# Connector_to_Connector.net
KiCad netlist of a schematic drawn in Altium Designer
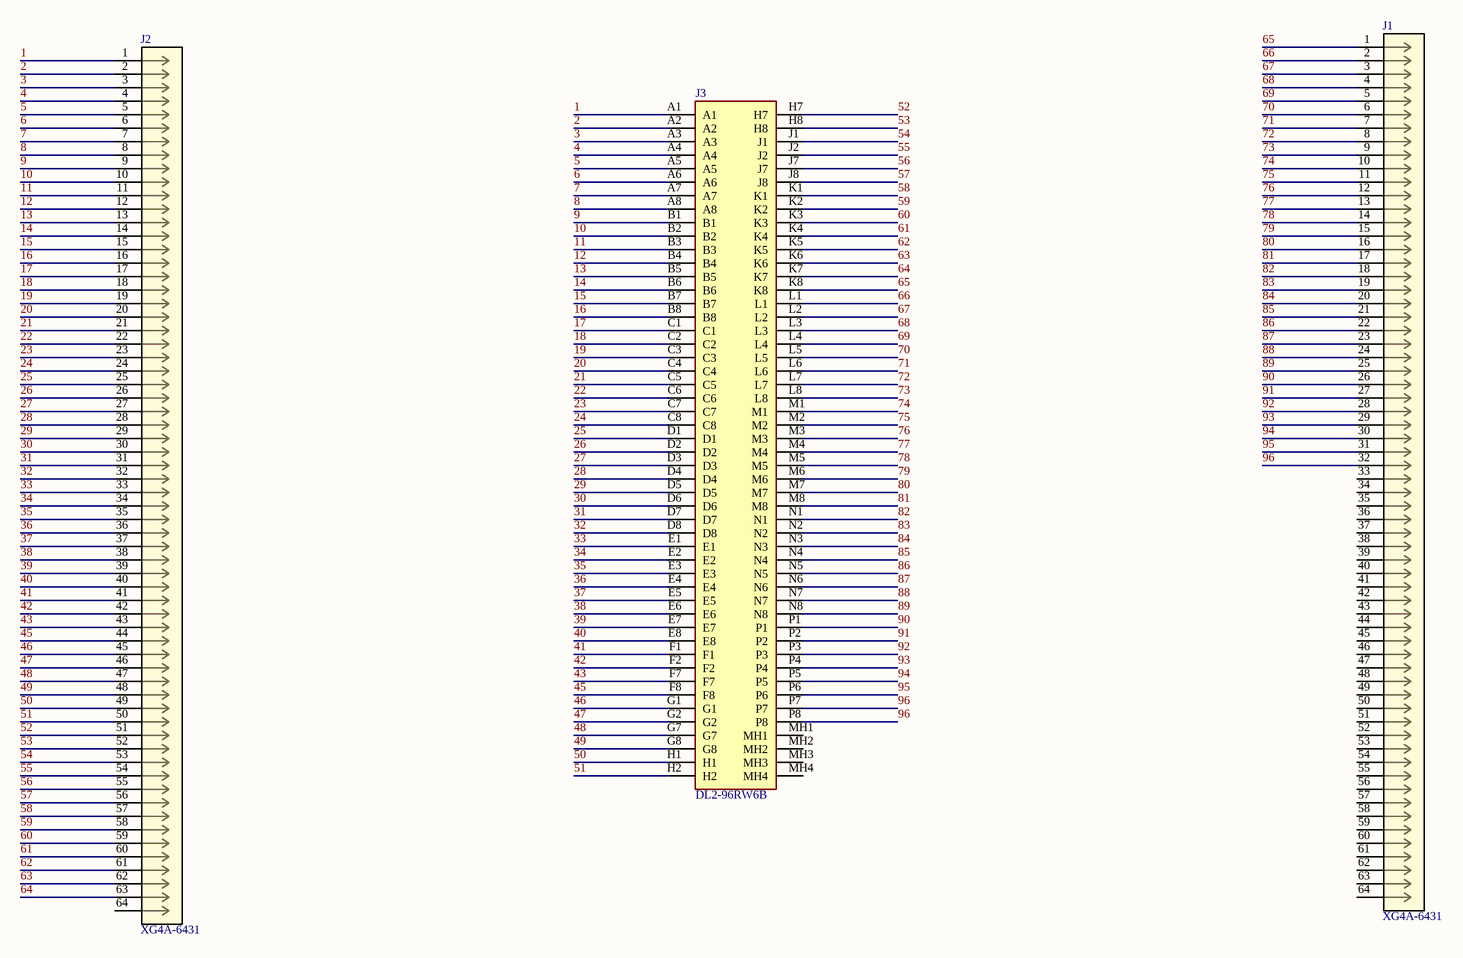
[diagram p0: Connector to Connector.SchDoc]

(export (version "E")
  (design (tool "Eeschema 10.0.6"))
  (components
    (comp (ref "J1")
      (value "XG4A-6431")
      (footprint "CONN_XG4A-6431_OMR")
      (description "No Description Available")
      (fields (field (name "COPYRIGHT") "Copyright (C) 2023 Ultra Librarian. All rights reserved."))
      (libsource (lib "XG4A-6431") (part "XG4A-6431"))
    )
    (comp (ref "J2")
      (value "XG4A-6431")
      (footprint "CONN_XG4A-6431_OMR")
      (description "No Description Available")
      (fields (field (name "COPYRIGHT") "Copyright (C) 2023 Ultra Librarian. All rights reserved."))
      (libsource (lib "XG4A-6431") (part "XG4A-6431"))
    )
    (comp (ref "J3")
      (value "DL2-96RW6B")
      (footprint "DL296RW6B")
      (description "Conn Rectangular SKT 96 POS 2.54mm Solder ST Thru-Hole Automotive")
      (libsource (lib "DL2-96RW6B") (part "DL2-96RW6B"))
    )
  )
  (nets
    (net (code "1") (name "/1") (class "Default")
      (node (ref "J2") (pin "1") (pinfunction "1_1") (pintype "passive"))
      (node (ref "J3") (pin "A1") (pinfunction "A1_A1") (pintype "passive"))
    )
    (net (code "2") (name "/2") (class "Default")
      (node (ref "J2") (pin "2") (pinfunction "2_2") (pintype "passive"))
      (node (ref "J3") (pin "A2") (pinfunction "A2_A2") (pintype "passive"))
    )
    (net (code "3") (name "/3") (class "Default")
      (node (ref "J2") (pin "3") (pinfunction "3_3") (pintype "passive"))
      (node (ref "J3") (pin "A3") (pinfunction "A3_A3") (pintype "passive"))
    )
    (net (code "4") (name "/4") (class "Default")
      (node (ref "J2") (pin "4") (pinfunction "4_4") (pintype "passive"))
      (node (ref "J3") (pin "A4") (pinfunction "A4_A4") (pintype "passive"))
    )
    (net (code "5") (name "/5") (class "Default")
      (node (ref "J2") (pin "5") (pinfunction "5_5") (pintype "passive"))
      (node (ref "J3") (pin "A5") (pinfunction "A5_A5") (pintype "passive"))
    )
    (net (code "6") (name "/6") (class "Default")
      (node (ref "J2") (pin "6") (pinfunction "6_6") (pintype "passive"))
      (node (ref "J3") (pin "A6") (pinfunction "A6_A6") (pintype "passive"))
    )
    (net (code "7") (name "/7") (class "Default")
      (node (ref "J2") (pin "7") (pinfunction "7_7") (pintype "passive"))
      (node (ref "J3") (pin "A7") (pinfunction "A7_A7") (pintype "passive"))
    )
    (net (code "8") (name "/8") (class "Default")
      (node (ref "J2") (pin "8") (pinfunction "8_8") (pintype "passive"))
      (node (ref "J3") (pin "A8") (pinfunction "A8_A8") (pintype "passive"))
    )
    (net (code "9") (name "/9") (class "Default")
      (node (ref "J2") (pin "9") (pinfunction "9_9") (pintype "passive"))
      (node (ref "J3") (pin "B1") (pinfunction "B1_B1") (pintype "passive"))
    )
    (net (code "10") (name "/10") (class "Default")
      (node (ref "J2") (pin "10") (pinfunction "10_10") (pintype "passive"))
      (node (ref "J3") (pin "B2") (pinfunction "B2_B2") (pintype "passive"))
    )
    (net (code "11") (name "/11") (class "Default")
      (node (ref "J2") (pin "11") (pinfunction "11_11") (pintype "passive"))
      (node (ref "J3") (pin "B3") (pinfunction "B3_B3") (pintype "passive"))
    )
    (net (code "12") (name "/12") (class "Default")
      (node (ref "J2") (pin "12") (pinfunction "12_12") (pintype "passive"))
      (node (ref "J3") (pin "B4") (pinfunction "B4_B4") (pintype "passive"))
    )
    (net (code "13") (name "/13") (class "Default")
      (node (ref "J2") (pin "13") (pinfunction "13_13") (pintype "passive"))
      (node (ref "J3") (pin "B5") (pinfunction "B5_B5") (pintype "passive"))
    )
    (net (code "14") (name "/14") (class "Default")
      (node (ref "J2") (pin "14") (pinfunction "14_14") (pintype "passive"))
      (node (ref "J3") (pin "B6") (pinfunction "B6_B6") (pintype "passive"))
    )
    (net (code "15") (name "/15") (class "Default")
      (node (ref "J2") (pin "15") (pinfunction "15_15") (pintype "passive"))
      (node (ref "J3") (pin "B7") (pinfunction "B7_B7") (pintype "passive"))
    )
    (net (code "16") (name "/16") (class "Default")
      (node (ref "J2") (pin "16") (pinfunction "16_16") (pintype "passive"))
      (node (ref "J3") (pin "B8") (pinfunction "B8_B8") (pintype "passive"))
    )
    (net (code "17") (name "/17") (class "Default")
      (node (ref "J2") (pin "17") (pinfunction "17_17") (pintype "passive"))
      (node (ref "J3") (pin "C1") (pinfunction "C1_C1") (pintype "passive"))
    )
    (net (code "18") (name "/18") (class "Default")
      (node (ref "J2") (pin "18") (pinfunction "18_18") (pintype "passive"))
      (node (ref "J3") (pin "C2") (pinfunction "C2_C2") (pintype "passive"))
    )
    (net (code "19") (name "/19") (class "Default")
      (node (ref "J2") (pin "19") (pinfunction "19_19") (pintype "passive"))
      (node (ref "J3") (pin "C3") (pinfunction "C3_C3") (pintype "passive"))
    )
    (net (code "20") (name "/20") (class "Default")
      (node (ref "J2") (pin "20") (pinfunction "20_20") (pintype "passive"))
      (node (ref "J3") (pin "C4") (pinfunction "C4_C4") (pintype "passive"))
    )
    (net (code "21") (name "/21") (class "Default")
      (node (ref "J2") (pin "21") (pinfunction "21_21") (pintype "passive"))
      (node (ref "J3") (pin "C5") (pinfunction "C5_C5") (pintype "passive"))
    )
    (net (code "22") (name "/22") (class "Default")
      (node (ref "J2") (pin "22") (pinfunction "22_22") (pintype "passive"))
      (node (ref "J3") (pin "C6") (pinfunction "C6_C6") (pintype "passive"))
    )
    (net (code "23") (name "/23") (class "Default")
      (node (ref "J2") (pin "23") (pinfunction "23_23") (pintype "passive"))
      (node (ref "J3") (pin "C7") (pinfunction "C7_C7") (pintype "passive"))
    )
    (net (code "24") (name "/24") (class "Default")
      (node (ref "J2") (pin "24") (pinfunction "24_24") (pintype "passive"))
      (node (ref "J3") (pin "C8") (pinfunction "C8_C8") (pintype "passive"))
    )
    (net (code "25") (name "/25") (class "Default")
      (node (ref "J2") (pin "25") (pinfunction "25_25") (pintype "passive"))
      (node (ref "J3") (pin "D1") (pinfunction "D1_D1") (pintype "passive"))
    )
    (net (code "26") (name "/26") (class "Default")
      (node (ref "J2") (pin "26") (pinfunction "26_26") (pintype "passive"))
      (node (ref "J3") (pin "D2") (pinfunction "D2_D2") (pintype "passive"))
    )
    (net (code "27") (name "/27") (class "Default")
      (node (ref "J2") (pin "27") (pinfunction "27_27") (pintype "passive"))
      (node (ref "J3") (pin "D3") (pinfunction "D3_D3") (pintype "passive"))
    )
    (net (code "28") (name "/28") (class "Default")
      (node (ref "J2") (pin "28") (pinfunction "28_28") (pintype "passive"))
      (node (ref "J3") (pin "D4") (pinfunction "D4_D4") (pintype "passive"))
    )
    (net (code "29") (name "/29") (class "Default")
      (node (ref "J2") (pin "29") (pinfunction "29_29") (pintype "passive"))
      (node (ref "J3") (pin "D5") (pinfunction "D5_D5") (pintype "passive"))
    )
    (net (code "30") (name "/30") (class "Default")
      (node (ref "J2") (pin "30") (pinfunction "30_30") (pintype "passive"))
      (node (ref "J3") (pin "D6") (pinfunction "D6_D6") (pintype "passive"))
    )
    (net (code "31") (name "/31") (class "Default")
      (node (ref "J2") (pin "31") (pinfunction "31_31") (pintype "passive"))
      (node (ref "J3") (pin "D7") (pinfunction "D7_D7") (pintype "passive"))
    )
    (net (code "32") (name "/32") (class "Default")
      (node (ref "J2") (pin "32") (pinfunction "32_32") (pintype "passive"))
      (node (ref "J3") (pin "D8") (pinfunction "D8_D8") (pintype "passive"))
    )
    (net (code "33") (name "/33") (class "Default")
      (node (ref "J2") (pin "33") (pinfunction "33_33") (pintype "passive"))
      (node (ref "J3") (pin "E1") (pinfunction "E1_E1") (pintype "passive"))
    )
    (net (code "34") (name "/34") (class "Default")
      (node (ref "J2") (pin "34") (pinfunction "34_34") (pintype "passive"))
      (node (ref "J3") (pin "E2") (pinfunction "E2_E2") (pintype "passive"))
    )
    (net (code "35") (name "/35") (class "Default")
      (node (ref "J2") (pin "35") (pinfunction "35_35") (pintype "passive"))
      (node (ref "J3") (pin "E3") (pinfunction "E3_E3") (pintype "passive"))
    )
    (net (code "36") (name "/36") (class "Default")
      (node (ref "J2") (pin "36") (pinfunction "36_36") (pintype "passive"))
      (node (ref "J3") (pin "E4") (pinfunction "E4_E4") (pintype "passive"))
    )
    (net (code "37") (name "/37") (class "Default")
      (node (ref "J2") (pin "37") (pinfunction "37_37") (pintype "passive"))
      (node (ref "J3") (pin "E5") (pinfunction "E5_E5") (pintype "passive"))
    )
    (net (code "38") (name "/38") (class "Default")
      (node (ref "J2") (pin "38") (pinfunction "38_38") (pintype "passive"))
      (node (ref "J3") (pin "E6") (pinfunction "E6_E6") (pintype "passive"))
    )
    (net (code "39") (name "/39") (class "Default")
      (node (ref "J2") (pin "39") (pinfunction "39_39") (pintype "passive"))
      (node (ref "J3") (pin "E7") (pinfunction "E7_E7") (pintype "passive"))
    )
    (net (code "40") (name "/40") (class "Default")
      (node (ref "J2") (pin "40") (pinfunction "40_40") (pintype "passive"))
      (node (ref "J3") (pin "E8") (pinfunction "E8_E8") (pintype "passive"))
    )
    (net (code "41") (name "/41") (class "Default")
      (node (ref "J2") (pin "41") (pinfunction "41_41") (pintype "passive"))
      (node (ref "J3") (pin "F1") (pinfunction "F1_F1") (pintype "passive"))
    )
    (net (code "42") (name "/42") (class "Default")
      (node (ref "J2") (pin "42") (pinfunction "42_42") (pintype "passive"))
      (node (ref "J3") (pin "F2") (pinfunction "F2_F2") (pintype "passive"))
    )
    (net (code "43") (name "/43") (class "Default")
      (node (ref "J2") (pin "43") (pinfunction "43_43") (pintype "passive"))
      (node (ref "J3") (pin "F7") (pinfunction "F7_F7") (pintype "passive"))
    )
    (net (code "44") (name "/45") (class "Default")
      (node (ref "J2") (pin "44") (pinfunction "44_44") (pintype "passive"))
      (node (ref "J3") (pin "F8") (pinfunction "F8_F8") (pintype "passive"))
    )
    (net (code "45") (name "/46") (class "Default")
      (node (ref "J2") (pin "45") (pinfunction "45_45") (pintype "passive"))
      (node (ref "J3") (pin "G1") (pinfunction "G1_G1") (pintype "passive"))
    )
    (net (code "46") (name "/47") (class "Default")
      (node (ref "J2") (pin "46") (pinfunction "46_46") (pintype "passive"))
      (node (ref "J3") (pin "G2") (pinfunction "G2_G2") (pintype "passive"))
    )
    (net (code "47") (name "/48") (class "Default")
      (node (ref "J2") (pin "47") (pinfunction "47_47") (pintype "passive"))
      (node (ref "J3") (pin "G7") (pinfunction "G7_G7") (pintype "passive"))
    )
    (net (code "48") (name "/49") (class "Default")
      (node (ref "J2") (pin "48") (pinfunction "48_48") (pintype "passive"))
      (node (ref "J3") (pin "G8") (pinfunction "G8_G8") (pintype "passive"))
    )
    (net (code "49") (name "/50") (class "Default")
      (node (ref "J2") (pin "49") (pinfunction "49_49") (pintype "passive"))
      (node (ref "J3") (pin "H1") (pinfunction "H1_H1") (pintype "passive"))
    )
    (net (code "50") (name "/51") (class "Default")
      (node (ref "J2") (pin "50") (pinfunction "50_50") (pintype "passive"))
      (node (ref "J3") (pin "H2") (pinfunction "H2_H2") (pintype "passive"))
    )
    (net (code "51") (name "/52") (class "Default")
      (node (ref "J2") (pin "51") (pinfunction "51_51") (pintype "passive"))
      (node (ref "J3") (pin "H7") (pinfunction "H7_H7") (pintype "passive"))
    )
    (net (code "52") (name "/53") (class "Default")
      (node (ref "J2") (pin "52") (pinfunction "52_52") (pintype "passive"))
      (node (ref "J3") (pin "H8") (pinfunction "H8_H8") (pintype "passive"))
    )
    (net (code "53") (name "/54") (class "Default")
      (node (ref "J2") (pin "53") (pinfunction "53_53") (pintype "passive"))
      (node (ref "J3") (pin "J1") (pinfunction "J1_J1") (pintype "passive"))
    )
    (net (code "54") (name "/55") (class "Default")
      (node (ref "J2") (pin "54") (pinfunction "54_54") (pintype "passive"))
      (node (ref "J3") (pin "J2") (pinfunction "J2_J2") (pintype "passive"))
    )
    (net (code "55") (name "/56") (class "Default")
      (node (ref "J2") (pin "55") (pinfunction "55_55") (pintype "passive"))
      (node (ref "J3") (pin "J7") (pinfunction "J7_J7") (pintype "passive"))
    )
    (net (code "56") (name "/57") (class "Default")
      (node (ref "J2") (pin "56") (pinfunction "56_56") (pintype "passive"))
      (node (ref "J3") (pin "J8") (pinfunction "J8_J8") (pintype "passive"))
    )
    (net (code "57") (name "/58") (class "Default")
      (node (ref "J2") (pin "57") (pinfunction "57_57") (pintype "passive"))
      (node (ref "J3") (pin "K1") (pinfunction "K1_K1") (pintype "passive"))
    )
    (net (code "58") (name "/59") (class "Default")
      (node (ref "J2") (pin "58") (pinfunction "58_58") (pintype "passive"))
      (node (ref "J3") (pin "K2") (pinfunction "K2_K2") (pintype "passive"))
    )
    (net (code "59") (name "/60") (class "Default")
      (node (ref "J2") (pin "59") (pinfunction "59_59") (pintype "passive"))
      (node (ref "J3") (pin "K3") (pinfunction "K3_K3") (pintype "passive"))
    )
    (net (code "60") (name "/61") (class "Default")
      (node (ref "J2") (pin "60") (pinfunction "60_60") (pintype "passive"))
      (node (ref "J3") (pin "K4") (pinfunction "K4_K4") (pintype "passive"))
    )
    (net (code "61") (name "/62") (class "Default")
      (node (ref "J2") (pin "61") (pinfunction "61_61") (pintype "passive"))
      (node (ref "J3") (pin "K5") (pinfunction "K5_K5") (pintype "passive"))
    )
    (net (code "62") (name "/63") (class "Default")
      (node (ref "J2") (pin "62") (pinfunction "62_62") (pintype "passive"))
      (node (ref "J3") (pin "K6") (pinfunction "K6_K6") (pintype "passive"))
    )
    (net (code "63") (name "/64") (class "Default")
      (node (ref "J2") (pin "63") (pinfunction "63_63") (pintype "passive"))
      (node (ref "J3") (pin "K7") (pinfunction "K7_K7") (pintype "passive"))
    )
    (net (code "64") (name "/65") (class "Default")
      (node (ref "J1") (pin "1") (pinfunction "1_1") (pintype "passive"))
      (node (ref "J3") (pin "K8") (pinfunction "K8_K8") (pintype "passive"))
    )
    (net (code "65") (name "/66") (class "Default")
      (node (ref "J1") (pin "2") (pinfunction "2_2") (pintype "passive"))
      (node (ref "J3") (pin "L1") (pinfunction "L1_L1") (pintype "passive"))
    )
    (net (code "66") (name "/67") (class "Default")
      (node (ref "J1") (pin "3") (pinfunction "3_3") (pintype "passive"))
      (node (ref "J3") (pin "L2") (pinfunction "L2_L2") (pintype "passive"))
    )
    (net (code "67") (name "/68") (class "Default")
      (node (ref "J1") (pin "4") (pinfunction "4_4") (pintype "passive"))
      (node (ref "J3") (pin "L3") (pinfunction "L3_L3") (pintype "passive"))
    )
    (net (code "68") (name "/69") (class "Default")
      (node (ref "J1") (pin "5") (pinfunction "5_5") (pintype "passive"))
      (node (ref "J3") (pin "L4") (pinfunction "L4_L4") (pintype "passive"))
    )
    (net (code "69") (name "/70") (class "Default")
      (node (ref "J1") (pin "6") (pinfunction "6_6") (pintype "passive"))
      (node (ref "J3") (pin "L5") (pinfunction "L5_L5") (pintype "passive"))
    )
    (net (code "70") (name "/71") (class "Default")
      (node (ref "J1") (pin "7") (pinfunction "7_7") (pintype "passive"))
      (node (ref "J3") (pin "L6") (pinfunction "L6_L6") (pintype "passive"))
    )
    (net (code "71") (name "/72") (class "Default")
      (node (ref "J1") (pin "8") (pinfunction "8_8") (pintype "passive"))
      (node (ref "J3") (pin "L7") (pinfunction "L7_L7") (pintype "passive"))
    )
    (net (code "72") (name "/73") (class "Default")
      (node (ref "J1") (pin "9") (pinfunction "9_9") (pintype "passive"))
      (node (ref "J3") (pin "L8") (pinfunction "L8_L8") (pintype "passive"))
    )
    (net (code "73") (name "/74") (class "Default")
      (node (ref "J1") (pin "10") (pinfunction "10_10") (pintype "passive"))
      (node (ref "J3") (pin "M1") (pinfunction "M1_M1") (pintype "passive"))
    )
    (net (code "74") (name "/75") (class "Default")
      (node (ref "J1") (pin "11") (pinfunction "11_11") (pintype "passive"))
      (node (ref "J3") (pin "M2") (pinfunction "M2_M2") (pintype "passive"))
    )
    (net (code "75") (name "/76") (class "Default")
      (node (ref "J1") (pin "12") (pinfunction "12_12") (pintype "passive"))
      (node (ref "J3") (pin "M3") (pinfunction "M3_M3") (pintype "passive"))
    )
    (net (code "76") (name "/77") (class "Default")
      (node (ref "J1") (pin "13") (pinfunction "13_13") (pintype "passive"))
      (node (ref "J3") (pin "M4") (pinfunction "M4_M4") (pintype "passive"))
    )
    (net (code "77") (name "/78") (class "Default")
      (node (ref "J1") (pin "14") (pinfunction "14_14") (pintype "passive"))
      (node (ref "J3") (pin "M5") (pinfunction "M5_M5") (pintype "passive"))
    )
    (net (code "78") (name "/79") (class "Default")
      (node (ref "J1") (pin "15") (pinfunction "15_15") (pintype "passive"))
      (node (ref "J3") (pin "M6") (pinfunction "M6_M6") (pintype "passive"))
    )
    (net (code "79") (name "/80") (class "Default")
      (node (ref "J1") (pin "16") (pinfunction "16_16") (pintype "passive"))
      (node (ref "J3") (pin "M7") (pinfunction "M7_M7") (pintype "passive"))
    )
    (net (code "80") (name "/81") (class "Default")
      (node (ref "J1") (pin "17") (pinfunction "17_17") (pintype "passive"))
      (node (ref "J3") (pin "M8") (pinfunction "M8_M8") (pintype "passive"))
    )
    (net (code "81") (name "/82") (class "Default")
      (node (ref "J1") (pin "18") (pinfunction "18_18") (pintype "passive"))
      (node (ref "J3") (pin "N1") (pinfunction "N1_N1") (pintype "passive"))
    )
    (net (code "82") (name "/83") (class "Default")
      (node (ref "J1") (pin "19") (pinfunction "19_19") (pintype "passive"))
      (node (ref "J3") (pin "N2") (pinfunction "N2_N2") (pintype "passive"))
    )
    (net (code "83") (name "/84") (class "Default")
      (node (ref "J1") (pin "20") (pinfunction "20_20") (pintype "passive"))
      (node (ref "J3") (pin "N3") (pinfunction "N3_N3") (pintype "passive"))
    )
    (net (code "84") (name "/85") (class "Default")
      (node (ref "J1") (pin "21") (pinfunction "21_21") (pintype "passive"))
      (node (ref "J3") (pin "N4") (pinfunction "N4_N4") (pintype "passive"))
    )
    (net (code "85") (name "/86") (class "Default")
      (node (ref "J1") (pin "22") (pinfunction "22_22") (pintype "passive"))
      (node (ref "J3") (pin "N5") (pinfunction "N5_N5") (pintype "passive"))
    )
    (net (code "86") (name "/87") (class "Default")
      (node (ref "J1") (pin "23") (pinfunction "23_23") (pintype "passive"))
      (node (ref "J3") (pin "N6") (pinfunction "N6_N6") (pintype "passive"))
    )
    (net (code "87") (name "/88") (class "Default")
      (node (ref "J1") (pin "24") (pinfunction "24_24") (pintype "passive"))
      (node (ref "J3") (pin "N7") (pinfunction "N7_N7") (pintype "passive"))
    )
    (net (code "88") (name "/89") (class "Default")
      (node (ref "J1") (pin "25") (pinfunction "25_25") (pintype "passive"))
      (node (ref "J3") (pin "N8") (pinfunction "N8_N8") (pintype "passive"))
    )
    (net (code "89") (name "/90") (class "Default")
      (node (ref "J1") (pin "26") (pinfunction "26_26") (pintype "passive"))
      (node (ref "J3") (pin "P1") (pinfunction "P1_P1") (pintype "passive"))
    )
    (net (code "90") (name "/91") (class "Default")
      (node (ref "J1") (pin "27") (pinfunction "27_27") (pintype "passive"))
      (node (ref "J3") (pin "P2") (pinfunction "P2_P2") (pintype "passive"))
    )
    (net (code "91") (name "/92") (class "Default")
      (node (ref "J1") (pin "28") (pinfunction "28_28") (pintype "passive"))
      (node (ref "J3") (pin "P3") (pinfunction "P3_P3") (pintype "passive"))
    )
    (net (code "92") (name "/93") (class "Default")
      (node (ref "J1") (pin "29") (pinfunction "29_29") (pintype "passive"))
      (node (ref "J3") (pin "P4") (pinfunction "P4_P4") (pintype "passive"))
    )
    (net (code "93") (name "/94") (class "Default")
      (node (ref "J1") (pin "30") (pinfunction "30_30") (pintype "passive"))
      (node (ref "J3") (pin "P5") (pinfunction "P5_P5") (pintype "passive"))
    )
    (net (code "94") (name "/95") (class "Default")
      (node (ref "J1") (pin "31") (pinfunction "31_31") (pintype "passive"))
      (node (ref "J3") (pin "P6") (pinfunction "P6_P6") (pintype "passive"))
    )
    (net (code "95") (name "/96") (class "Default")
      (node (ref "J1") (pin "32") (pinfunction "32_32") (pintype "passive"))
      (node (ref "J3") (pin "P7") (pinfunction "P7_P7") (pintype "passive"))
      (node (ref "J3") (pin "P8") (pinfunction "P8_P8") (pintype "passive"))
    )
    (net (code "96") (name "unconnected-(J1-Pad33)") (class "Default")
      (node (ref "J1") (pin "33") (pinfunction "33_33") (pintype "passive"))
    )
    (net (code "97") (name "unconnected-(J1-Pad34)") (class "Default")
      (node (ref "J1") (pin "34") (pinfunction "34_34") (pintype "passive"))
    )
    (net (code "98") (name "unconnected-(J1-Pad35)") (class "Default")
      (node (ref "J1") (pin "35") (pinfunction "35_35") (pintype "passive"))
    )
    (net (code "99") (name "unconnected-(J1-Pad36)") (class "Default")
      (node (ref "J1") (pin "36") (pinfunction "36_36") (pintype "passive"))
    )
    (net (code "100") (name "unconnected-(J1-Pad37)") (class "Default")
      (node (ref "J1") (pin "37") (pinfunction "37_37") (pintype "passive"))
    )
    (net (code "101") (name "unconnected-(J1-Pad38)") (class "Default")
      (node (ref "J1") (pin "38") (pinfunction "38_38") (pintype "passive"))
    )
    (net (code "102") (name "unconnected-(J1-Pad39)") (class "Default")
      (node (ref "J1") (pin "39") (pinfunction "39_39") (pintype "passive"))
    )
    (net (code "103") (name "unconnected-(J1-Pad40)") (class "Default")
      (node (ref "J1") (pin "40") (pinfunction "40_40") (pintype "passive"))
    )
    (net (code "104") (name "unconnected-(J1-Pad41)") (class "Default")
      (node (ref "J1") (pin "41") (pinfunction "41_41") (pintype "passive"))
    )
    (net (code "105") (name "unconnected-(J1-Pad42)") (class "Default")
      (node (ref "J1") (pin "42") (pinfunction "42_42") (pintype "passive"))
    )
    (net (code "106") (name "unconnected-(J1-Pad43)") (class "Default")
      (node (ref "J1") (pin "43") (pinfunction "43_43") (pintype "passive"))
    )
    (net (code "107") (name "unconnected-(J1-Pad44)") (class "Default")
      (node (ref "J1") (pin "44") (pinfunction "44_44") (pintype "passive"))
    )
    (net (code "108") (name "unconnected-(J1-Pad45)") (class "Default")
      (node (ref "J1") (pin "45") (pinfunction "45_45") (pintype "passive"))
    )
    (net (code "109") (name "unconnected-(J1-Pad46)") (class "Default")
      (node (ref "J1") (pin "46") (pinfunction "46_46") (pintype "passive"))
    )
    (net (code "110") (name "unconnected-(J1-Pad47)") (class "Default")
      (node (ref "J1") (pin "47") (pinfunction "47_47") (pintype "passive"))
    )
    (net (code "111") (name "unconnected-(J1-Pad48)") (class "Default")
      (node (ref "J1") (pin "48") (pinfunction "48_48") (pintype "passive"))
    )
    (net (code "112") (name "unconnected-(J1-Pad49)") (class "Default")
      (node (ref "J1") (pin "49") (pinfunction "49_49") (pintype "passive"))
    )
    (net (code "113") (name "unconnected-(J1-Pad50)") (class "Default")
      (node (ref "J1") (pin "50") (pinfunction "50_50") (pintype "passive"))
    )
    (net (code "114") (name "unconnected-(J1-Pad51)") (class "Default")
      (node (ref "J1") (pin "51") (pinfunction "51_51") (pintype "passive"))
    )
    (net (code "115") (name "unconnected-(J1-Pad52)") (class "Default")
      (node (ref "J1") (pin "52") (pinfunction "52_52") (pintype "passive"))
    )
    (net (code "116") (name "unconnected-(J1-Pad53)") (class "Default")
      (node (ref "J1") (pin "53") (pinfunction "53_53") (pintype "passive"))
    )
    (net (code "117") (name "unconnected-(J1-Pad54)") (class "Default")
      (node (ref "J1") (pin "54") (pinfunction "54_54") (pintype "passive"))
    )
    (net (code "118") (name "unconnected-(J1-Pad55)") (class "Default")
      (node (ref "J1") (pin "55") (pinfunction "55_55") (pintype "passive"))
    )
    (net (code "119") (name "unconnected-(J1-Pad56)") (class "Default")
      (node (ref "J1") (pin "56") (pinfunction "56_56") (pintype "passive"))
    )
    (net (code "120") (name "unconnected-(J1-Pad57)") (class "Default")
      (node (ref "J1") (pin "57") (pinfunction "57_57") (pintype "passive"))
    )
    (net (code "121") (name "unconnected-(J1-Pad58)") (class "Default")
      (node (ref "J1") (pin "58") (pinfunction "58_58") (pintype "passive"))
    )
    (net (code "122") (name "unconnected-(J1-Pad59)") (class "Default")
      (node (ref "J1") (pin "59") (pinfunction "59_59") (pintype "passive"))
    )
    (net (code "123") (name "unconnected-(J1-Pad60)") (class "Default")
      (node (ref "J1") (pin "60") (pinfunction "60_60") (pintype "passive"))
    )
    (net (code "124") (name "unconnected-(J1-Pad61)") (class "Default")
      (node (ref "J1") (pin "61") (pinfunction "61_61") (pintype "passive"))
    )
    (net (code "125") (name "unconnected-(J1-Pad62)") (class "Default")
      (node (ref "J1") (pin "62") (pinfunction "62_62") (pintype "passive"))
    )
    (net (code "126") (name "unconnected-(J1-Pad63)") (class "Default")
      (node (ref "J1") (pin "63") (pinfunction "63_63") (pintype "passive"))
    )
    (net (code "127") (name "unconnected-(J1-Pad64)") (class "Default")
      (node (ref "J1") (pin "64") (pinfunction "64_64") (pintype "passive"))
    )
    (net (code "128") (name "unconnected-(J2-Pad64)") (class "Default")
      (node (ref "J2") (pin "64") (pinfunction "64_64") (pintype "passive"))
    )
    (net (code "129") (name "unconnected-(J3-PadMH1)") (class "Default")
      (node (ref "J3") (pin "MH1") (pinfunction "MH1_MH1") (pintype "passive"))
    )
    (net (code "130") (name "unconnected-(J3-PadMH2)") (class "Default")
      (node (ref "J3") (pin "MH2") (pinfunction "MH2_MH2") (pintype "passive"))
    )
    (net (code "131") (name "unconnected-(J3-PadMH3)") (class "Default")
      (node (ref "J3") (pin "MH3") (pinfunction "MH3_MH3") (pintype "passive"))
    )
    (net (code "132") (name "unconnected-(J3-PadMH4)") (class "Default")
      (node (ref "J3") (pin "MH4") (pinfunction "MH4_MH4") (pintype "passive"))
    )
  )
)
